# Schematic3.net
KiCad netlist of a schematic drawn in EAGLE
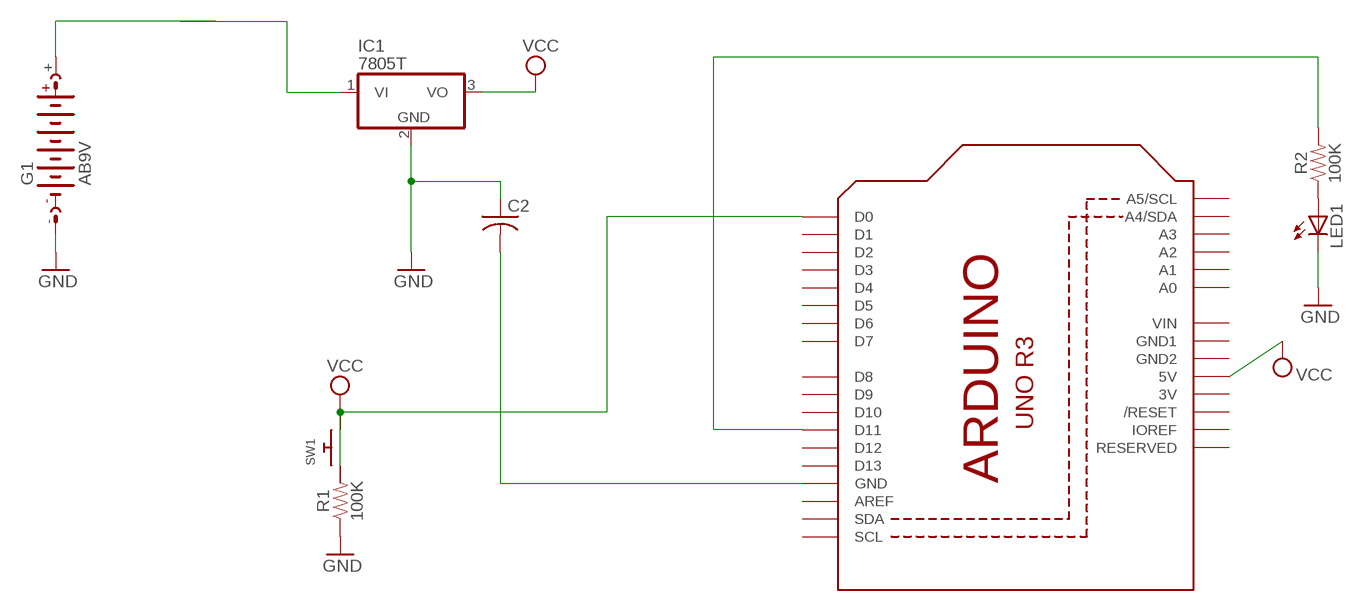
[diagram p0: schematic, sheet 1]

(export (version "E")
  (design (tool "Eeschema 10.0.6"))
  (components
    (comp (ref "C2")
      (value "C-US025-024X044")
      (footprint "eagle-import:C025-024X044")
      (libsource (lib "eagle-import") (part "C-US025-024X044"))
    )
    (comp (ref "G1")
      (value "AB9V")
      (footprint "eagle-import:AB9V")
      (libsource (lib "eagle-import") (part "AB9V"))
    )
    (comp (ref "IC1")
      (value "7805T")
      (footprint "eagle-import:TO220H")
      (libsource (lib "eagle-import") (part "78T05"))
    )
    (comp (ref "LED1")
      (value "LED")
      (footprint "eagle-import:SMARTLED-TTW")
      (libsource (lib "eagle-import") (part "LED"))
    )
    (comp (ref "R1")
      (value "100K")
      (footprint "eagle-import:0402")
      (libsource (lib "eagle-import") (part "100KOHM-0402-1/16W-1%"))
    )
    (comp (ref "R2")
      (value "100K")
      (footprint "eagle-import:0402")
      (libsource (lib "eagle-import") (part "100KOHM-0402-1/16W-1%"))
    )
    (comp (ref "SW1")
      (value "SWITCH_PUSHBUTTONSOFTTOUCHSMD_SJ")
      (footprint "eagle-import:PUSHBUTTON_SMD_SJ")
      (libsource (lib "eagle-import") (part "SWITCH_PUSHBUTTONSOFTTOUCHSMD_SJ"))
    )
    (comp (ref "U1")
      (value "ARDUINOR3-BPLACE")
      (footprint "eagle-import:ARDUINOR3-BPLACE")
      (libsource (lib "eagle-import") (part "ARDUINOR3-BPLACE"))
    )
  )
  (nets
    (net (code "1") (name "/3V") (class "Default")
      (node (ref "U1") (pin "3V") (pinfunction "3V_3V") (pintype "power_in"))
    )
    (net (code "2") (name "/GND1") (class "Default")
      (node (ref "U1") (pin "GND1") (pinfunction "GND1_GND1") (pintype "power_in"))
    )
    (net (code "3") (name "/GND2") (class "Default")
      (node (ref "U1") (pin "GND2") (pinfunction "GND2_GND2") (pintype "power_in"))
    )
    (net (code "4") (name "/VIN") (class "Default")
      (node (ref "U1") (pin "VIN") (pinfunction "VIN_VIN") (pintype "power_in"))
    )
    (net (code "5") (name "GND") (class "Default")
      (node (ref "C2") (pin "1") (pinfunction "1_1") (pintype "passive"))
      (node (ref "G1") (pin "-") (pinfunction "-_-") (pintype "passive"))
      (node (ref "IC1") (pin "2") (pinfunction "GND_2") (pintype "passive"))
      (node (ref "LED1") (pin "C@1") (pinfunction "C_C@1") (pintype "passive"))
      (node (ref "R1") (pin "1") (pinfunction "1_1") (pintype "passive"))
    )
    (net (code "6") (name "Net-(C2-Pad2)") (class "Default")
      (node (ref "C2") (pin "2") (pinfunction "2_2") (pintype "passive"))
      (node (ref "U1") (pin "GND") (pinfunction "GND_GND") (pintype "power_in"))
    )
    (net (code "7") (name "Net-(LED1-A)") (class "Default")
      (node (ref "LED1") (pin "A@1") (pinfunction "A_A@1") (pintype "passive"))
      (node (ref "R2") (pin "1") (pinfunction "1_1") (pintype "passive"))
    )
    (net (code "8") (name "Net-(R2-Pad2)") (class "Default")
      (node (ref "R2") (pin "2") (pinfunction "2_2") (pintype "passive"))
      (node (ref "U1") (pin "D11") (pinfunction "D11_D11") (pintype "bidirectional"))
    )
    (net (code "9") (name "VCC") (class "Default")
      (node (ref "IC1") (pin "3") (pinfunction "VO_3") (pintype "passive"))
      (node (ref "R1") (pin "2") (pinfunction "2_2") (pintype "passive"))
      (node (ref "SW1") (pin "P$2") (pinfunction "P$2_P$2") (pintype "passive"))
      (node (ref "U1") (pin "5V") (pinfunction "5V_5V") (pintype "power_in"))
      (node (ref "U1") (pin "D0") (pinfunction "D0_D0") (pintype "bidirectional"))
    )
    (net (code "10") (name "unconnected-(G1-Pad+)") (class "Default")
      (node (ref "G1") (pin "+") (pinfunction "+_+") (pintype "passive"))
    )
    (net (code "11") (name "unconnected-(IC1-VI-Pad1)") (class "Default")
      (node (ref "IC1") (pin "1") (pinfunction "VI_1") (pintype "input"))
    )
    (net (code "12") (name "unconnected-(SW1-PadP$1)") (class "Default")
      (node (ref "SW1") (pin "P$1") (pinfunction "P$1_P$1") (pintype "passive"))
    )
    (net (code "13") (name "unconnected-(U1-A4{slash}SDA-PadA4)") (class "Default")
      (node (ref "U1") (pin "A4") (pinfunction "A4/SDA_A4") (pintype "bidirectional"))
    )
    (net (code "14") (name "unconnected-(U1-A5{slash}SCL-PadA5)") (class "Default")
      (node (ref "U1") (pin "A5") (pinfunction "A5/SCL_A5") (pintype "bidirectional"))
    )
    (net (code "15") (name "unconnected-(U1-PadA0)") (class "Default")
      (node (ref "U1") (pin "A0") (pinfunction "A0_A0") (pintype "bidirectional"))
    )
    (net (code "16") (name "unconnected-(U1-PadA1)") (class "Default")
      (node (ref "U1") (pin "A1") (pinfunction "A1_A1") (pintype "bidirectional"))
    )
    (net (code "17") (name "unconnected-(U1-PadA2)") (class "Default")
      (node (ref "U1") (pin "A2") (pinfunction "A2_A2") (pintype "bidirectional"))
    )
    (net (code "18") (name "unconnected-(U1-PadA3)") (class "Default")
      (node (ref "U1") (pin "A3") (pinfunction "A3_A3") (pintype "bidirectional"))
    )
    (net (code "19") (name "unconnected-(U1-PadAREF)") (class "Default")
      (node (ref "U1") (pin "AREF") (pinfunction "AREF_AREF") (pintype "bidirectional"))
    )
    (net (code "20") (name "unconnected-(U1-PadD1)") (class "Default")
      (node (ref "U1") (pin "D1") (pinfunction "D1_D1") (pintype "bidirectional"))
    )
    (net (code "21") (name "unconnected-(U1-PadD2)") (class "Default")
      (node (ref "U1") (pin "D2") (pinfunction "D2_D2") (pintype "bidirectional"))
    )
    (net (code "22") (name "unconnected-(U1-PadD3)") (class "Default")
      (node (ref "U1") (pin "D3") (pinfunction "D3_D3") (pintype "bidirectional"))
    )
    (net (code "23") (name "unconnected-(U1-PadD4)") (class "Default")
      (node (ref "U1") (pin "D4") (pinfunction "D4_D4") (pintype "bidirectional"))
    )
    (net (code "24") (name "unconnected-(U1-PadD5)") (class "Default")
      (node (ref "U1") (pin "D5") (pinfunction "D5_D5") (pintype "bidirectional"))
    )
    (net (code "25") (name "unconnected-(U1-PadD6)") (class "Default")
      (node (ref "U1") (pin "D6") (pinfunction "D6_D6") (pintype "bidirectional"))
    )
    (net (code "26") (name "unconnected-(U1-PadD7)") (class "Default")
      (node (ref "U1") (pin "D7") (pinfunction "D7_D7") (pintype "bidirectional"))
    )
    (net (code "27") (name "unconnected-(U1-PadD8)") (class "Default")
      (node (ref "U1") (pin "D8") (pinfunction "D8_D8") (pintype "bidirectional"))
    )
    (net (code "28") (name "unconnected-(U1-PadD9)") (class "Default")
      (node (ref "U1") (pin "D9") (pinfunction "D9_D9") (pintype "bidirectional"))
    )
    (net (code "29") (name "unconnected-(U1-PadD10)") (class "Default")
      (node (ref "U1") (pin "D10") (pinfunction "D10_D10") (pintype "bidirectional"))
    )
    (net (code "30") (name "unconnected-(U1-PadD12)") (class "Default")
      (node (ref "U1") (pin "D12") (pinfunction "D12_D12") (pintype "bidirectional"))
    )
    (net (code "31") (name "unconnected-(U1-PadD13)") (class "Default")
      (node (ref "U1") (pin "D13") (pinfunction "D13_D13") (pintype "bidirectional"))
    )
    (net (code "32") (name "unconnected-(U1-PadIOREF)") (class "Default")
      (node (ref "U1") (pin "IOREF") (pinfunction "IOREF_IOREF") (pintype "output"))
    )
    (net (code "33") (name "unconnected-(U1-PadRESERVED)") (class "Default")
      (node (ref "U1") (pin "RESERVED") (pinfunction "RESERVED_RESERVED") (pintype "no_connect"))
    )
    (net (code "34") (name "unconnected-(U1-PadSCL)") (class "Default")
      (node (ref "U1") (pin "SCL") (pinfunction "SCL_SCL") (pintype "bidirectional"))
    )
    (net (code "35") (name "unconnected-(U1-PadSDA)") (class "Default")
      (node (ref "U1") (pin "SDA") (pinfunction "SDA_SDA") (pintype "bidirectional"))
    )
    (net (code "36") (name "unconnected-(U1-{slash}RESET-PadRESET)") (class "Default")
      (node (ref "U1") (pin "RESET") (pinfunction "/RESET_RESET") (pintype "bidirectional"))
    )
  )
)
